# BCP_Experimental_1.net
KiCad netlist of a schematic drawn in EAGLE
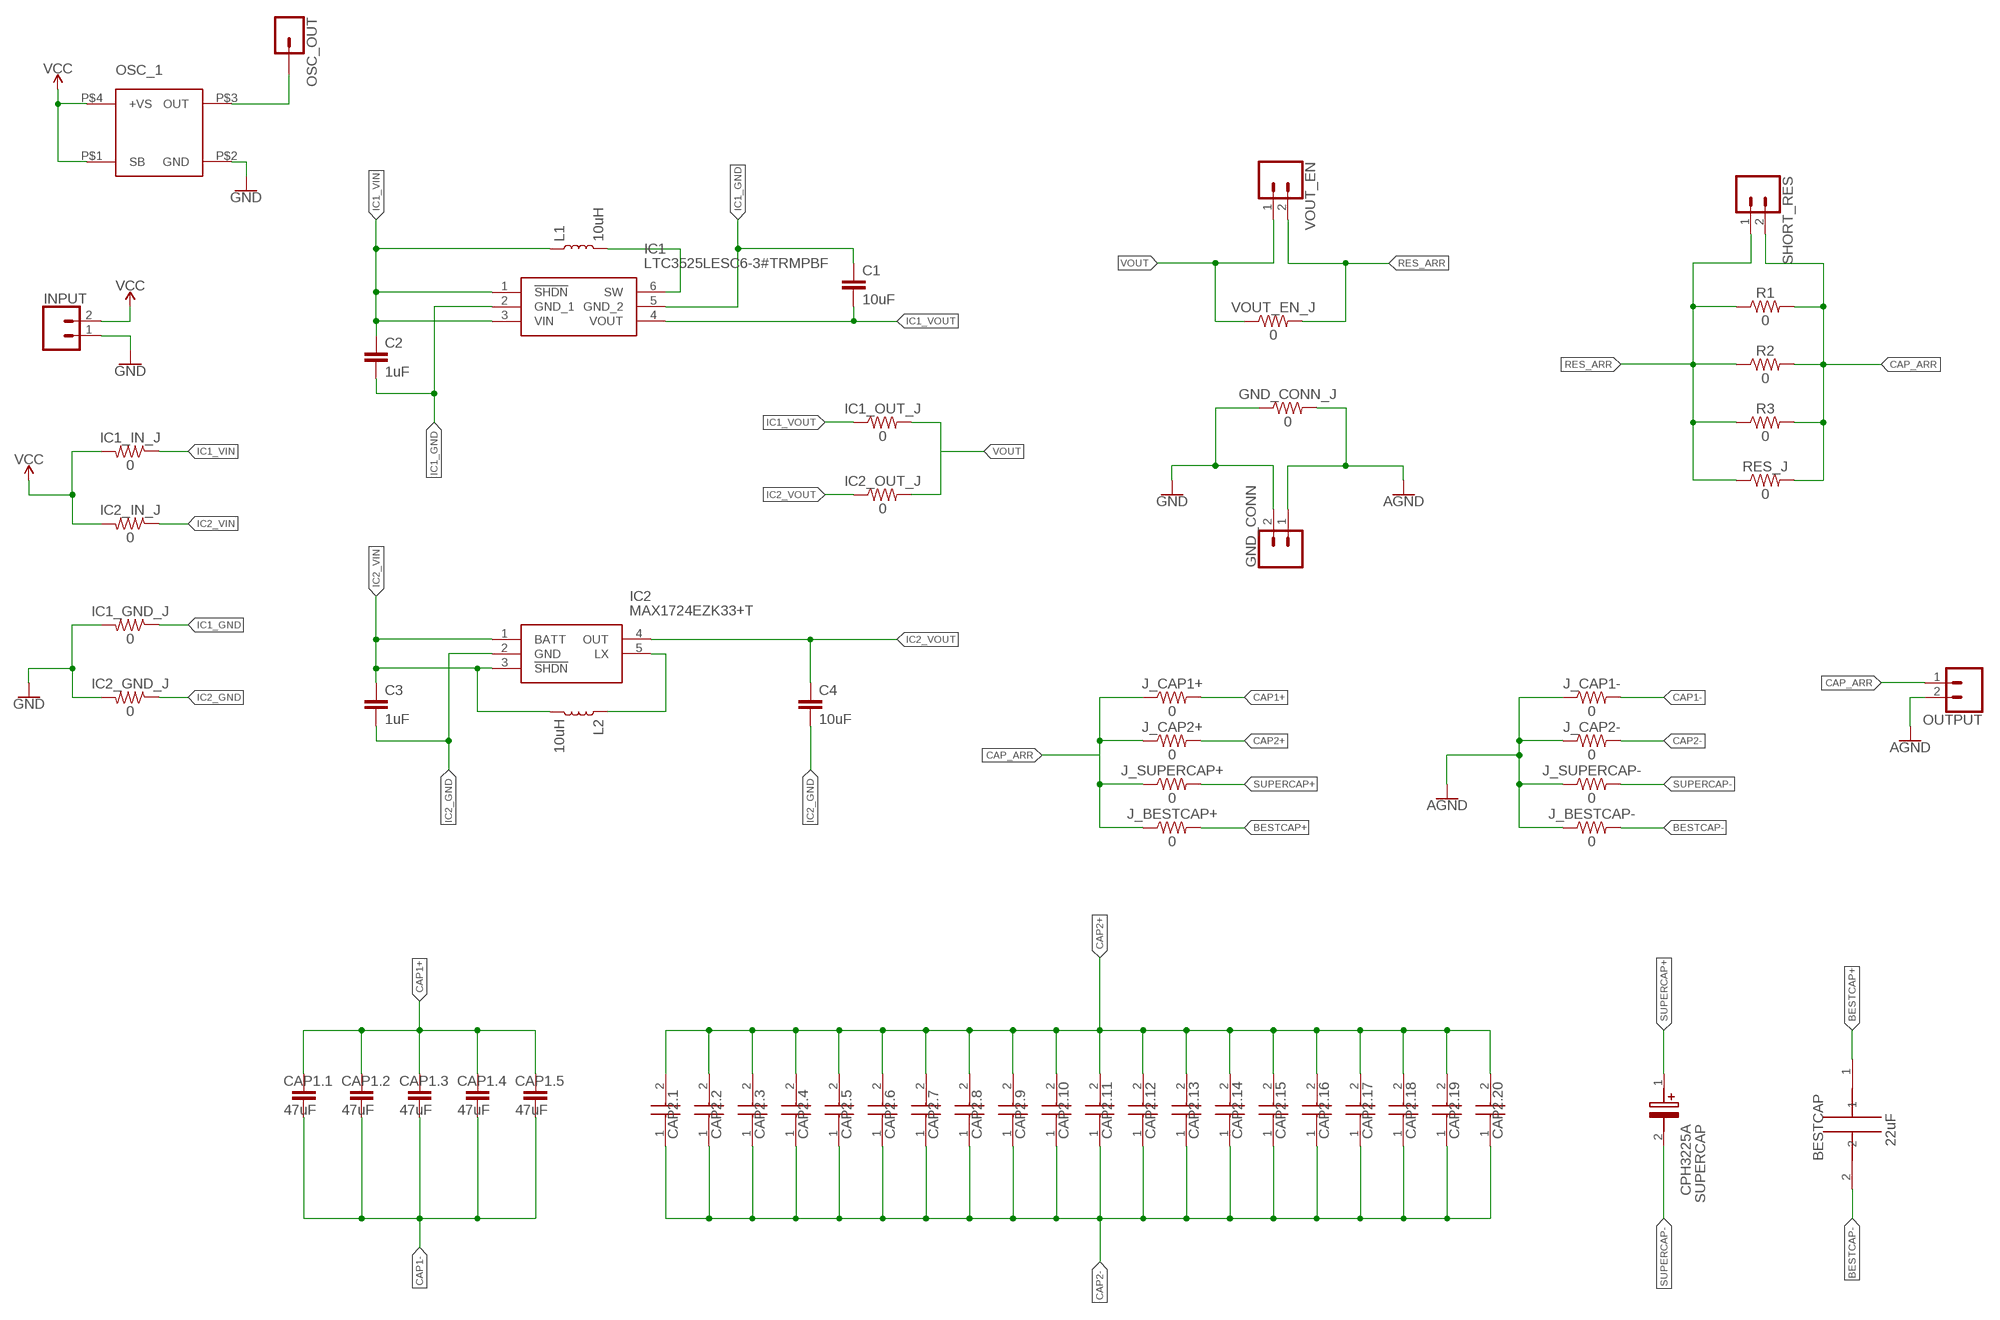
[diagram p0: schematic, sheet 1]

(export (version "E")
  (design (tool "Eeschema 10.0.6"))
  (components
    (comp (ref "BESTCAP")
      (value "BZ054B223ZNB")
      (footprint "eagle-import:BZ054B223ZNB")
      (libsource (lib "eagle-import") (part "BZ054B223ZNB"))
    )
    (comp (ref "C1")
      (value "10uF")
      (footprint "eagle-import:0603")
      (libsource (lib "eagle-import") (part "CAP-0603"))
    )
    (comp (ref "C2")
      (value "1uF")
      (footprint "eagle-import:0603")
      (libsource (lib "eagle-import") (part "CAP-0603"))
    )
    (comp (ref "C3")
      (value "1uF")
      (footprint "eagle-import:0603")
      (libsource (lib "eagle-import") (part "CAP-0603"))
    )
    (comp (ref "C4")
      (value "10uF")
      (footprint "eagle-import:0603")
      (libsource (lib "eagle-import") (part "CAP-0603"))
    )
    (comp (ref "CAP1.1")
      (value "47uF")
      (footprint "eagle-import:1206")
      (libsource (lib "eagle-import") (part "CAP-1206"))
    )
    (comp (ref "CAP1.2")
      (value "47uF")
      (footprint "eagle-import:1206")
      (libsource (lib "eagle-import") (part "CAP-1206"))
    )
    (comp (ref "CAP1.3")
      (value "47uF")
      (footprint "eagle-import:1206")
      (libsource (lib "eagle-import") (part "CAP-1206"))
    )
    (comp (ref "CAP1.4")
      (value "47uF")
      (footprint "eagle-import:1206")
      (libsource (lib "eagle-import") (part "CAP-1206"))
    )
    (comp (ref "CAP1.5")
      (value "47uF")
      (footprint "eagle-import:1206")
      (libsource (lib "eagle-import") (part "CAP-1206"))
    )
    (comp (ref "CAP2.1")
      (value "AMK432BJ477MM-T")
      (footprint "eagle-import:CAPC4532X270N")
      (fields (field (name "MOUSER_PART_NUMBER") "963-AMK432BJ477MM-T"))
      (libsource (lib "eagle-import") (part "AMK432BJ477MM-T"))
    )
    (comp (ref "CAP2.2")
      (value "AMK432BJ477MM-T")
      (footprint "eagle-import:CAPC4532X270N")
      (fields (field (name "MOUSER_PART_NUMBER") "963-AMK432BJ477MM-T"))
      (libsource (lib "eagle-import") (part "AMK432BJ477MM-T"))
    )
    (comp (ref "CAP2.3")
      (value "AMK432BJ477MM-T")
      (footprint "eagle-import:CAPC4532X270N")
      (fields (field (name "MOUSER_PART_NUMBER") "963-AMK432BJ477MM-T"))
      (libsource (lib "eagle-import") (part "AMK432BJ477MM-T"))
    )
    (comp (ref "CAP2.4")
      (value "AMK432BJ477MM-T")
      (footprint "eagle-import:CAPC4532X270N")
      (fields (field (name "MOUSER_PART_NUMBER") "963-AMK432BJ477MM-T"))
      (libsource (lib "eagle-import") (part "AMK432BJ477MM-T"))
    )
    (comp (ref "CAP2.5")
      (value "AMK432BJ477MM-T")
      (footprint "eagle-import:CAPC4532X270N")
      (fields (field (name "MOUSER_PART_NUMBER") "963-AMK432BJ477MM-T"))
      (libsource (lib "eagle-import") (part "AMK432BJ477MM-T"))
    )
    (comp (ref "CAP2.6")
      (value "AMK432BJ477MM-T")
      (footprint "eagle-import:CAPC4532X270N")
      (fields (field (name "MOUSER_PART_NUMBER") "963-AMK432BJ477MM-T"))
      (libsource (lib "eagle-import") (part "AMK432BJ477MM-T"))
    )
    (comp (ref "CAP2.7")
      (value "AMK432BJ477MM-T")
      (footprint "eagle-import:CAPC4532X270N")
      (fields (field (name "MOUSER_PART_NUMBER") "963-AMK432BJ477MM-T"))
      (libsource (lib "eagle-import") (part "AMK432BJ477MM-T"))
    )
    (comp (ref "CAP2.8")
      (value "AMK432BJ477MM-T")
      (footprint "eagle-import:CAPC4532X270N")
      (fields (field (name "MOUSER_PART_NUMBER") "963-AMK432BJ477MM-T"))
      (libsource (lib "eagle-import") (part "AMK432BJ477MM-T"))
    )
    (comp (ref "CAP2.9")
      (value "AMK432BJ477MM-T")
      (footprint "eagle-import:CAPC4532X270N")
      (fields (field (name "MOUSER_PART_NUMBER") "963-AMK432BJ477MM-T"))
      (libsource (lib "eagle-import") (part "AMK432BJ477MM-T"))
    )
    (comp (ref "CAP2.10")
      (value "AMK432BJ477MM-T")
      (footprint "eagle-import:CAPC4532X270N")
      (fields (field (name "MOUSER_PART_NUMBER") "963-AMK432BJ477MM-T"))
      (libsource (lib "eagle-import") (part "AMK432BJ477MM-T"))
    )
    (comp (ref "CAP2.11")
      (value "AMK432BJ477MM-T")
      (footprint "eagle-import:CAPC4532X270N")
      (fields (field (name "MOUSER_PART_NUMBER") "963-AMK432BJ477MM-T"))
      (libsource (lib "eagle-import") (part "AMK432BJ477MM-T"))
    )
    (comp (ref "CAP2.12")
      (value "AMK432BJ477MM-T")
      (footprint "eagle-import:CAPC4532X270N")
      (fields (field (name "MOUSER_PART_NUMBER") "963-AMK432BJ477MM-T"))
      (libsource (lib "eagle-import") (part "AMK432BJ477MM-T"))
    )
    (comp (ref "CAP2.13")
      (value "AMK432BJ477MM-T")
      (footprint "eagle-import:CAPC4532X270N")
      (fields (field (name "MOUSER_PART_NUMBER") "963-AMK432BJ477MM-T"))
      (libsource (lib "eagle-import") (part "AMK432BJ477MM-T"))
    )
    (comp (ref "CAP2.14")
      (value "AMK432BJ477MM-T")
      (footprint "eagle-import:CAPC4532X270N")
      (fields (field (name "MOUSER_PART_NUMBER") "963-AMK432BJ477MM-T"))
      (libsource (lib "eagle-import") (part "AMK432BJ477MM-T"))
    )
    (comp (ref "CAP2.15")
      (value "AMK432BJ477MM-T")
      (footprint "eagle-import:CAPC4532X270N")
      (fields (field (name "MOUSER_PART_NUMBER") "963-AMK432BJ477MM-T"))
      (libsource (lib "eagle-import") (part "AMK432BJ477MM-T"))
    )
    (comp (ref "CAP2.16")
      (value "AMK432BJ477MM-T")
      (footprint "eagle-import:CAPC4532X270N")
      (fields (field (name "MOUSER_PART_NUMBER") "963-AMK432BJ477MM-T"))
      (libsource (lib "eagle-import") (part "AMK432BJ477MM-T"))
    )
    (comp (ref "CAP2.17")
      (value "AMK432BJ477MM-T")
      (footprint "eagle-import:CAPC4532X270N")
      (fields (field (name "MOUSER_PART_NUMBER") "963-AMK432BJ477MM-T"))
      (libsource (lib "eagle-import") (part "AMK432BJ477MM-T"))
    )
    (comp (ref "CAP2.18")
      (value "AMK432BJ477MM-T")
      (footprint "eagle-import:CAPC4532X270N")
      (fields (field (name "MOUSER_PART_NUMBER") "963-AMK432BJ477MM-T"))
      (libsource (lib "eagle-import") (part "AMK432BJ477MM-T"))
    )
    (comp (ref "CAP2.19")
      (value "AMK432BJ477MM-T")
      (footprint "eagle-import:CAPC4532X270N")
      (fields (field (name "MOUSER_PART_NUMBER") "963-AMK432BJ477MM-T"))
      (libsource (lib "eagle-import") (part "AMK432BJ477MM-T"))
    )
    (comp (ref "CAP2.20")
      (value "AMK432BJ477MM-T")
      (footprint "eagle-import:CAPC4532X270N")
      (fields (field (name "MOUSER_PART_NUMBER") "963-AMK432BJ477MM-T"))
      (libsource (lib "eagle-import") (part "AMK432BJ477MM-T"))
    )
    (comp (ref "GND_CONN")
      (value "CONN_02")
      (footprint "eagle-import:1X02")
      (libsource (lib "eagle-import") (part "CONN_02"))
    )
    (comp (ref "GND_CONN_J")
      (value "0")
      (footprint "eagle-import:0402")
      (libsource (lib "eagle-import") (part "RESISTOR0402"))
    )
    (comp (ref "IC1")
      (value "LTC3525LESC6-3#TRMPBF")
      (footprint "eagle-import:SOT65P210X100-6N")
      (fields (field (name "MOUSER_PART_NUMBER") "584-C3525LESC6-3TMPF"))
      (libsource (lib "eagle-import") (part "LTC3525LESC6-3#TRMPBF"))
    )
    (comp (ref "IC1_GND_J")
      (value "0")
      (footprint "eagle-import:0402")
      (libsource (lib "eagle-import") (part "RESISTOR0402"))
    )
    (comp (ref "IC1_IN_J")
      (value "0")
      (footprint "eagle-import:0402")
      (libsource (lib "eagle-import") (part "RESISTOR0402"))
    )
    (comp (ref "IC1_OUT_J")
      (value "0")
      (footprint "eagle-import:0402")
      (libsource (lib "eagle-import") (part "RESISTOR0402"))
    )
    (comp (ref "IC2")
      (value "MAX1724EZK33+T")
      (footprint "eagle-import:SOT95P275X110-5N")
      (fields (field (name "MOUSER_PART_NUMBER") "700-MAX1724EZK33T"))
      (libsource (lib "eagle-import") (part "MAX1724EZK33+T"))
    )
    (comp (ref "IC2_GND_J")
      (value "0")
      (footprint "eagle-import:0402")
      (libsource (lib "eagle-import") (part "RESISTOR0402"))
    )
    (comp (ref "IC2_IN_J")
      (value "0")
      (footprint "eagle-import:0402")
      (libsource (lib "eagle-import") (part "RESISTOR0402"))
    )
    (comp (ref "IC2_OUT_J")
      (value "0")
      (footprint "eagle-import:0402")
      (libsource (lib "eagle-import") (part "RESISTOR0402"))
    )
    (comp (ref "INPUT")
      (value "CONN_02")
      (footprint "eagle-import:1X02")
      (libsource (lib "eagle-import") (part "CONN_02"))
    )
    (comp (ref "J_BESTCAP+")
      (value "0")
      (footprint "eagle-import:0402")
      (libsource (lib "eagle-import") (part "RESISTOR0402"))
    )
    (comp (ref "J_BESTCAP-")
      (value "0")
      (footprint "eagle-import:0402")
      (libsource (lib "eagle-import") (part "RESISTOR0402"))
    )
    (comp (ref "J_CAP1+")
      (value "0")
      (footprint "eagle-import:0402")
      (libsource (lib "eagle-import") (part "RESISTOR0402"))
    )
    (comp (ref "J_CAP1-")
      (value "0")
      (footprint "eagle-import:0402")
      (libsource (lib "eagle-import") (part "RESISTOR0402"))
    )
    (comp (ref "J_CAP2+")
      (value "0")
      (footprint "eagle-import:0402")
      (libsource (lib "eagle-import") (part "RESISTOR0402"))
    )
    (comp (ref "J_CAP2-")
      (value "0")
      (footprint "eagle-import:0402")
      (libsource (lib "eagle-import") (part "RESISTOR0402"))
    )
    (comp (ref "J_SUPERCAP+")
      (value "0")
      (footprint "eagle-import:0402")
      (libsource (lib "eagle-import") (part "RESISTOR0402"))
    )
    (comp (ref "J_SUPERCAP-")
      (value "0")
      (footprint "eagle-import:0402")
      (libsource (lib "eagle-import") (part "RESISTOR0402"))
    )
    (comp (ref "L1")
      (value "10uH")
      (footprint "eagle-import:0603")
      (libsource (lib "eagle-import") (part "INDUCTOR-0603-15NH"))
    )
    (comp (ref "L2")
      (value "10uH")
      (footprint "eagle-import:0603")
      (libsource (lib "eagle-import") (part "INDUCTOR-0603-15NH"))
    )
    (comp (ref "OSC_1")
      (value "830202536501")
      (footprint "eagle-import:830202536501")
      (libsource (lib "eagle-import") (part "830202536501"))
    )
    (comp (ref "OSC_OUT")
      (value "CONN_01")
      (footprint "eagle-import:1X01")
      (libsource (lib "eagle-import") (part "CONN_01"))
    )
    (comp (ref "OUTPUT")
      (value "CONN_02")
      (footprint "eagle-import:1X02")
      (libsource (lib "eagle-import") (part "CONN_02"))
    )
    (comp (ref "R1")
      (value "0")
      (footprint "eagle-import:0603")
      (libsource (lib "eagle-import") (part "RESISTOR0603"))
    )
    (comp (ref "R2")
      (value "0")
      (footprint "eagle-import:0603")
      (libsource (lib "eagle-import") (part "RESISTOR0603"))
    )
    (comp (ref "R3")
      (value "0")
      (footprint "eagle-import:0603")
      (libsource (lib "eagle-import") (part "RESISTOR0603"))
    )
    (comp (ref "RES_J")
      (value "0")
      (footprint "eagle-import:0402")
      (libsource (lib "eagle-import") (part "RESISTOR0402"))
    )
    (comp (ref "SHORT_RES")
      (value "CONN_02")
      (footprint "eagle-import:1X02")
      (libsource (lib "eagle-import") (part "CONN_02"))
    )
    (comp (ref "SUPERCAP")
      (value "CPH3225A")
      (footprint "eagle-import:CPH3225A")
      (fields (field (name "MOUSER_PART_NUMBER") "628-CPH3225A"))
      (libsource (lib "eagle-import") (part "CPH3225A"))
    )
    (comp (ref "VOUT_EN")
      (value "CONN_02")
      (footprint "eagle-import:1X02")
      (libsource (lib "eagle-import") (part "CONN_02"))
    )
    (comp (ref "VOUT_EN_J")
      (value "0")
      (footprint "eagle-import:0402")
      (libsource (lib "eagle-import") (part "RESISTOR0402"))
    )
  )
  (nets
    (net (code "1") (name "AGND") (class "Default")
      (node (ref "GND_CONN") (pin "1") (pinfunction "1_1") (pintype "passive"))
      (node (ref "GND_CONN_J") (pin "2") (pinfunction "2_2") (pintype "passive"))
      (node (ref "J_BESTCAP-") (pin "1") (pinfunction "1_1") (pintype "passive"))
      (node (ref "J_CAP1-") (pin "1") (pinfunction "1_1") (pintype "passive"))
      (node (ref "J_CAP2-") (pin "1") (pinfunction "1_1") (pintype "passive"))
      (node (ref "J_SUPERCAP-") (pin "1") (pinfunction "1_1") (pintype "passive"))
      (node (ref "OUTPUT") (pin "2") (pinfunction "2_2") (pintype "passive"))
    )
    (net (code "2") (name "BESTCAP+") (class "Default")
      (node (ref "BESTCAP") (pin "1") (pinfunction "1_1") (pintype "bidirectional"))
      (node (ref "J_BESTCAP+") (pin "2") (pinfunction "2_2") (pintype "passive"))
    )
    (net (code "3") (name "BESTCAP-") (class "Default")
      (node (ref "BESTCAP") (pin "2") (pinfunction "2_2") (pintype "bidirectional"))
      (node (ref "J_BESTCAP-") (pin "2") (pinfunction "2_2") (pintype "passive"))
    )
    (net (code "4") (name "CAP1+") (class "Default")
      (node (ref "CAP1.1") (pin "1") (pinfunction "1_1") (pintype "passive"))
      (node (ref "CAP1.2") (pin "1") (pinfunction "1_1") (pintype "passive"))
      (node (ref "CAP1.3") (pin "1") (pinfunction "1_1") (pintype "passive"))
      (node (ref "CAP1.4") (pin "1") (pinfunction "1_1") (pintype "passive"))
      (node (ref "CAP1.5") (pin "1") (pinfunction "1_1") (pintype "passive"))
      (node (ref "J_CAP1+") (pin "2") (pinfunction "2_2") (pintype "passive"))
    )
    (net (code "5") (name "CAP1-") (class "Default")
      (node (ref "CAP1.1") (pin "2") (pinfunction "2_2") (pintype "passive"))
      (node (ref "CAP1.2") (pin "2") (pinfunction "2_2") (pintype "passive"))
      (node (ref "CAP1.3") (pin "2") (pinfunction "2_2") (pintype "passive"))
      (node (ref "CAP1.4") (pin "2") (pinfunction "2_2") (pintype "passive"))
      (node (ref "CAP1.5") (pin "2") (pinfunction "2_2") (pintype "passive"))
      (node (ref "J_CAP1-") (pin "2") (pinfunction "2_2") (pintype "passive"))
    )
    (net (code "6") (name "CAP2+") (class "Default")
      (node (ref "CAP2.1") (pin "2") (pinfunction "2_2") (pintype "bidirectional"))
      (node (ref "CAP2.10") (pin "2") (pinfunction "2_2") (pintype "bidirectional"))
      (node (ref "CAP2.11") (pin "2") (pinfunction "2_2") (pintype "bidirectional"))
      (node (ref "CAP2.12") (pin "2") (pinfunction "2_2") (pintype "bidirectional"))
      (node (ref "CAP2.13") (pin "2") (pinfunction "2_2") (pintype "bidirectional"))
      (node (ref "CAP2.14") (pin "2") (pinfunction "2_2") (pintype "bidirectional"))
      (node (ref "CAP2.15") (pin "2") (pinfunction "2_2") (pintype "bidirectional"))
      (node (ref "CAP2.16") (pin "2") (pinfunction "2_2") (pintype "bidirectional"))
      (node (ref "CAP2.17") (pin "2") (pinfunction "2_2") (pintype "bidirectional"))
      (node (ref "CAP2.18") (pin "2") (pinfunction "2_2") (pintype "bidirectional"))
      (node (ref "CAP2.19") (pin "2") (pinfunction "2_2") (pintype "bidirectional"))
      (node (ref "CAP2.2") (pin "2") (pinfunction "2_2") (pintype "bidirectional"))
      (node (ref "CAP2.20") (pin "2") (pinfunction "2_2") (pintype "bidirectional"))
      (node (ref "CAP2.3") (pin "2") (pinfunction "2_2") (pintype "bidirectional"))
      (node (ref "CAP2.4") (pin "2") (pinfunction "2_2") (pintype "bidirectional"))
      (node (ref "CAP2.5") (pin "2") (pinfunction "2_2") (pintype "bidirectional"))
      (node (ref "CAP2.6") (pin "2") (pinfunction "2_2") (pintype "bidirectional"))
      (node (ref "CAP2.7") (pin "2") (pinfunction "2_2") (pintype "bidirectional"))
      (node (ref "CAP2.8") (pin "2") (pinfunction "2_2") (pintype "bidirectional"))
      (node (ref "CAP2.9") (pin "2") (pinfunction "2_2") (pintype "bidirectional"))
      (node (ref "J_CAP2+") (pin "2") (pinfunction "2_2") (pintype "passive"))
    )
    (net (code "7") (name "CAP2-") (class "Default")
      (node (ref "CAP2.1") (pin "1") (pinfunction "1_1") (pintype "bidirectional"))
      (node (ref "CAP2.10") (pin "1") (pinfunction "1_1") (pintype "bidirectional"))
      (node (ref "CAP2.11") (pin "1") (pinfunction "1_1") (pintype "bidirectional"))
      (node (ref "CAP2.12") (pin "1") (pinfunction "1_1") (pintype "bidirectional"))
      (node (ref "CAP2.13") (pin "1") (pinfunction "1_1") (pintype "bidirectional"))
      (node (ref "CAP2.14") (pin "1") (pinfunction "1_1") (pintype "bidirectional"))
      (node (ref "CAP2.15") (pin "1") (pinfunction "1_1") (pintype "bidirectional"))
      (node (ref "CAP2.16") (pin "1") (pinfunction "1_1") (pintype "bidirectional"))
      (node (ref "CAP2.17") (pin "1") (pinfunction "1_1") (pintype "bidirectional"))
      (node (ref "CAP2.18") (pin "1") (pinfunction "1_1") (pintype "bidirectional"))
      (node (ref "CAP2.19") (pin "1") (pinfunction "1_1") (pintype "bidirectional"))
      (node (ref "CAP2.2") (pin "1") (pinfunction "1_1") (pintype "bidirectional"))
      (node (ref "CAP2.20") (pin "1") (pinfunction "1_1") (pintype "bidirectional"))
      (node (ref "CAP2.3") (pin "1") (pinfunction "1_1") (pintype "bidirectional"))
      (node (ref "CAP2.4") (pin "1") (pinfunction "1_1") (pintype "bidirectional"))
      (node (ref "CAP2.5") (pin "1") (pinfunction "1_1") (pintype "bidirectional"))
      (node (ref "CAP2.6") (pin "1") (pinfunction "1_1") (pintype "bidirectional"))
      (node (ref "CAP2.7") (pin "1") (pinfunction "1_1") (pintype "bidirectional"))
      (node (ref "CAP2.8") (pin "1") (pinfunction "1_1") (pintype "bidirectional"))
      (node (ref "CAP2.9") (pin "1") (pinfunction "1_1") (pintype "bidirectional"))
      (node (ref "J_CAP2-") (pin "2") (pinfunction "2_2") (pintype "passive"))
    )
    (net (code "8") (name "CAP_ARR") (class "Default")
      (node (ref "J_BESTCAP+") (pin "1") (pinfunction "1_1") (pintype "passive"))
      (node (ref "J_CAP1+") (pin "1") (pinfunction "1_1") (pintype "passive"))
      (node (ref "J_CAP2+") (pin "1") (pinfunction "1_1") (pintype "passive"))
      (node (ref "J_SUPERCAP+") (pin "1") (pinfunction "1_1") (pintype "passive"))
      (node (ref "OUTPUT") (pin "1") (pinfunction "1_1") (pintype "passive"))
      (node (ref "R1") (pin "2") (pinfunction "2_2") (pintype "passive"))
      (node (ref "R2") (pin "2") (pinfunction "2_2") (pintype "passive"))
      (node (ref "R3") (pin "2") (pinfunction "2_2") (pintype "passive"))
      (node (ref "RES_J") (pin "2") (pinfunction "2_2") (pintype "passive"))
      (node (ref "SHORT_RES") (pin "2") (pinfunction "2_2") (pintype "passive"))
    )
    (net (code "9") (name "GND") (class "Default")
      (node (ref "GND_CONN") (pin "2") (pinfunction "2_2") (pintype "passive"))
      (node (ref "GND_CONN_J") (pin "1") (pinfunction "1_1") (pintype "passive"))
      (node (ref "IC1_GND_J") (pin "2") (pinfunction "2_2") (pintype "passive"))
      (node (ref "IC2_GND_J") (pin "2") (pinfunction "2_2") (pintype "passive"))
      (node (ref "INPUT") (pin "1") (pinfunction "1_1") (pintype "passive"))
      (node (ref "OSC_1") (pin "P$2") (pinfunction "GND_P$2") (pintype "bidirectional"))
    )
    (net (code "10") (name "IC1_GND") (class "Default")
      (node (ref "C1") (pin "1") (pinfunction "1_1") (pintype "passive"))
      (node (ref "C2") (pin "2") (pinfunction "2_2") (pintype "passive"))
      (node (ref "IC1") (pin "2") (pinfunction "GND_1_2") (pintype "bidirectional"))
      (node (ref "IC1") (pin "5") (pinfunction "GND_2_5") (pintype "bidirectional"))
      (node (ref "IC1_GND_J") (pin "1") (pinfunction "1_1") (pintype "passive"))
    )
    (net (code "11") (name "IC1_VIN") (class "Default")
      (node (ref "C2") (pin "1") (pinfunction "1_1") (pintype "passive"))
      (node (ref "IC1") (pin "1") (pinfunction "~{SHDN}_1") (pintype "bidirectional"))
      (node (ref "IC1") (pin "3") (pinfunction "VIN_3") (pintype "bidirectional"))
      (node (ref "IC1_IN_J") (pin "1") (pinfunction "1_1") (pintype "passive"))
      (node (ref "L1") (pin "1") (pinfunction "1_1") (pintype "passive"))
    )
    (net (code "12") (name "IC1_VOUT") (class "Default")
      (node (ref "C1") (pin "2") (pinfunction "2_2") (pintype "passive"))
      (node (ref "IC1") (pin "4") (pinfunction "VOUT_4") (pintype "bidirectional"))
      (node (ref "IC1_OUT_J") (pin "1") (pinfunction "1_1") (pintype "passive"))
    )
    (net (code "13") (name "IC2_GND") (class "Default")
      (node (ref "C3") (pin "2") (pinfunction "2_2") (pintype "passive"))
      (node (ref "C4") (pin "2") (pinfunction "2_2") (pintype "passive"))
      (node (ref "IC2") (pin "2") (pinfunction "GND_2") (pintype "power_in"))
      (node (ref "IC2_GND_J") (pin "1") (pinfunction "1_1") (pintype "passive"))
    )
    (net (code "14") (name "IC2_VIN") (class "Default")
      (node (ref "C3") (pin "1") (pinfunction "1_1") (pintype "passive"))
      (node (ref "IC2") (pin "1") (pinfunction "BATT_1") (pintype "bidirectional"))
      (node (ref "IC2") (pin "3") (pinfunction "~{SHDN}_3") (pintype "bidirectional"))
      (node (ref "IC2_IN_J") (pin "1") (pinfunction "1_1") (pintype "passive"))
      (node (ref "L2") (pin "2") (pinfunction "2_2") (pintype "passive"))
    )
    (net (code "15") (name "IC2_VOUT") (class "Default")
      (node (ref "C4") (pin "1") (pinfunction "1_1") (pintype "passive"))
      (node (ref "IC2") (pin "4") (pinfunction "OUT_4") (pintype "output"))
      (node (ref "IC2_OUT_J") (pin "1") (pinfunction "1_1") (pintype "passive"))
    )
    (net (code "16") (name "Net-(IC1-SW)") (class "Default")
      (node (ref "IC1") (pin "6") (pinfunction "SW_6") (pintype "bidirectional"))
      (node (ref "L1") (pin "2") (pinfunction "2_2") (pintype "passive"))
    )
    (net (code "17") (name "Net-(IC2-LX)") (class "Default")
      (node (ref "IC2") (pin "5") (pinfunction "LX_5") (pintype "bidirectional"))
      (node (ref "L2") (pin "1") (pinfunction "1_1") (pintype "passive"))
    )
    (net (code "18") (name "Net-(OSC_1-OUT)") (class "Default")
      (node (ref "OSC_1") (pin "P$3") (pinfunction "OUT_P$3") (pintype "bidirectional"))
      (node (ref "OSC_OUT") (pin "1") (pinfunction "1_1") (pintype "passive"))
    )
    (net (code "19") (name "RES_ARR") (class "Default")
      (node (ref "R1") (pin "1") (pinfunction "1_1") (pintype "passive"))
      (node (ref "R2") (pin "1") (pinfunction "1_1") (pintype "passive"))
      (node (ref "R3") (pin "1") (pinfunction "1_1") (pintype "passive"))
      (node (ref "RES_J") (pin "1") (pinfunction "1_1") (pintype "passive"))
      (node (ref "SHORT_RES") (pin "1") (pinfunction "1_1") (pintype "passive"))
      (node (ref "VOUT_EN") (pin "2") (pinfunction "2_2") (pintype "passive"))
      (node (ref "VOUT_EN_J") (pin "2") (pinfunction "2_2") (pintype "passive"))
    )
    (net (code "20") (name "SUPERCAP+") (class "Default")
      (node (ref "J_SUPERCAP+") (pin "2") (pinfunction "2_2") (pintype "passive"))
      (node (ref "SUPERCAP") (pin "1") (pinfunction "+_1") (pintype "bidirectional"))
    )
    (net (code "21") (name "SUPERCAP-") (class "Default")
      (node (ref "J_SUPERCAP-") (pin "2") (pinfunction "2_2") (pintype "passive"))
      (node (ref "SUPERCAP") (pin "2") (pinfunction "-_2") (pintype "bidirectional"))
    )
    (net (code "22") (name "VCC") (class "Default")
      (node (ref "IC1_IN_J") (pin "2") (pinfunction "2_2") (pintype "passive"))
      (node (ref "IC2_IN_J") (pin "2") (pinfunction "2_2") (pintype "passive"))
      (node (ref "INPUT") (pin "2") (pinfunction "2_2") (pintype "passive"))
      (node (ref "OSC_1") (pin "P$1") (pinfunction "SB_P$1") (pintype "bidirectional"))
      (node (ref "OSC_1") (pin "P$4") (pinfunction "+VS_P$4") (pintype "bidirectional"))
    )
    (net (code "23") (name "VOUT") (class "Default")
      (node (ref "IC1_OUT_J") (pin "2") (pinfunction "2_2") (pintype "passive"))
      (node (ref "IC2_OUT_J") (pin "2") (pinfunction "2_2") (pintype "passive"))
      (node (ref "VOUT_EN") (pin "1") (pinfunction "1_1") (pintype "passive"))
      (node (ref "VOUT_EN_J") (pin "1") (pinfunction "1_1") (pintype "passive"))
    )
  )
)
